# Key.net
KiCad netlist of a schematic drawn in Altium Designer
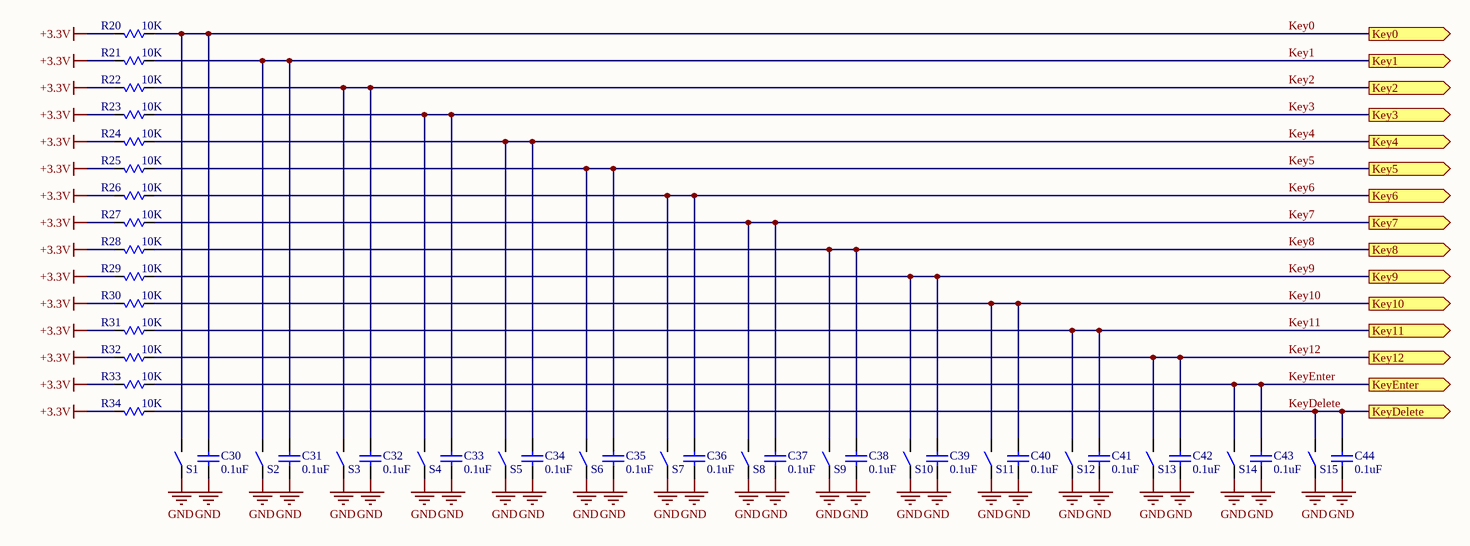
[diagram p0: 电子脚铐手持式主控板_Key.SchDoc]

(export (version "E")
  (design (tool "Eeschema 10.0.6"))
  (components
    (comp (ref "C30")
      (value "0.1uF")
      (footprint "C0603")
      (description "Capacitor")
      (fields (field (name "PUBLISHER") "Altium Limited"))
      (libsource (lib "Miscellaneous Devices") (part "Cap"))
    )
    (comp (ref "C31")
      (value "0.1uF")
      (footprint "C0603")
      (description "Capacitor")
      (fields (field (name "PUBLISHER") "Altium Limited"))
      (libsource (lib "Miscellaneous Devices") (part "Cap"))
    )
    (comp (ref "C32")
      (value "0.1uF")
      (footprint "C0603")
      (description "Capacitor")
      (fields (field (name "PUBLISHER") "Altium Limited"))
      (libsource (lib "Miscellaneous Devices") (part "Cap"))
    )
    (comp (ref "C33")
      (value "0.1uF")
      (footprint "C0603")
      (description "Capacitor")
      (fields (field (name "PUBLISHER") "Altium Limited"))
      (libsource (lib "Miscellaneous Devices") (part "Cap"))
    )
    (comp (ref "C34")
      (value "0.1uF")
      (footprint "C0603")
      (description "Capacitor")
      (fields (field (name "PUBLISHER") "Altium Limited"))
      (libsource (lib "Miscellaneous Devices") (part "Cap"))
    )
    (comp (ref "C35")
      (value "0.1uF")
      (footprint "C0603")
      (description "Capacitor")
      (fields (field (name "PUBLISHER") "Altium Limited"))
      (libsource (lib "Miscellaneous Devices") (part "Cap"))
    )
    (comp (ref "C36")
      (value "0.1uF")
      (footprint "C0603")
      (description "Capacitor")
      (fields (field (name "PUBLISHER") "Altium Limited"))
      (libsource (lib "Miscellaneous Devices") (part "Cap"))
    )
    (comp (ref "C37")
      (value "0.1uF")
      (footprint "C0603")
      (description "Capacitor")
      (fields (field (name "PUBLISHER") "Altium Limited"))
      (libsource (lib "Miscellaneous Devices") (part "Cap"))
    )
    (comp (ref "C38")
      (value "0.1uF")
      (footprint "C0603")
      (description "Capacitor")
      (fields (field (name "PUBLISHER") "Altium Limited"))
      (libsource (lib "Miscellaneous Devices") (part "Cap"))
    )
    (comp (ref "C39")
      (value "0.1uF")
      (footprint "C0603")
      (description "Capacitor")
      (fields (field (name "PUBLISHER") "Altium Limited"))
      (libsource (lib "Miscellaneous Devices") (part "Cap"))
    )
    (comp (ref "C40")
      (value "0.1uF")
      (footprint "C0603")
      (description "Capacitor")
      (fields (field (name "PUBLISHER") "Altium Limited"))
      (libsource (lib "Miscellaneous Devices") (part "Cap"))
    )
    (comp (ref "C41")
      (value "0.1uF")
      (footprint "C0603")
      (description "Capacitor")
      (fields (field (name "PUBLISHER") "Altium Limited"))
      (libsource (lib "Miscellaneous Devices") (part "Cap"))
    )
    (comp (ref "C42")
      (value "0.1uF")
      (footprint "C0603")
      (description "Capacitor")
      (fields (field (name "PUBLISHER") "Altium Limited"))
      (libsource (lib "Miscellaneous Devices") (part "Cap"))
    )
    (comp (ref "C43")
      (value "0.1uF")
      (footprint "C0603")
      (description "Capacitor")
      (fields (field (name "PUBLISHER") "Altium Limited"))
      (libsource (lib "Miscellaneous Devices") (part "Cap"))
    )
    (comp (ref "C44")
      (value "0.1uF")
      (footprint "C0603")
      (description "Capacitor")
      (fields (field (name "PUBLISHER") "Altium Limited"))
      (libsource (lib "Miscellaneous Devices") (part "Cap"))
    )
    (comp (ref "R20")
      (value "10K")
      (footprint "R0603")
      (description "Resistor")
      (fields (field (name "PUBLISHER") "Altium Limited"))
      (libsource (lib "Passive Components Class") (part "RES"))
    )
    (comp (ref "R21")
      (value "10K")
      (footprint "R0603")
      (description "Resistor")
      (fields (field (name "PUBLISHER") "Altium Limited"))
      (libsource (lib "Passive Components Class") (part "RES"))
    )
    (comp (ref "R22")
      (value "10K")
      (footprint "R0603")
      (description "Resistor")
      (fields (field (name "PUBLISHER") "Altium Limited"))
      (libsource (lib "Passive Components Class") (part "RES"))
    )
    (comp (ref "R23")
      (value "10K")
      (footprint "R0603")
      (description "Resistor")
      (fields (field (name "PUBLISHER") "Altium Limited"))
      (libsource (lib "Passive Components Class") (part "RES"))
    )
    (comp (ref "R24")
      (value "10K")
      (footprint "R0603")
      (description "Resistor")
      (fields (field (name "PUBLISHER") "Altium Limited"))
      (libsource (lib "Passive Components Class") (part "RES"))
    )
    (comp (ref "R25")
      (value "10K")
      (footprint "R0603")
      (description "Resistor")
      (fields (field (name "PUBLISHER") "Altium Limited"))
      (libsource (lib "Passive Components Class") (part "RES"))
    )
    (comp (ref "R26")
      (value "10K")
      (footprint "R0603")
      (description "Resistor")
      (fields (field (name "PUBLISHER") "Altium Limited"))
      (libsource (lib "Passive Components Class") (part "RES"))
    )
    (comp (ref "R27")
      (value "10K")
      (footprint "R0603")
      (description "Resistor")
      (fields (field (name "PUBLISHER") "Altium Limited"))
      (libsource (lib "Passive Components Class") (part "RES"))
    )
    (comp (ref "R28")
      (value "10K")
      (footprint "R0603")
      (description "Resistor")
      (fields (field (name "PUBLISHER") "Altium Limited"))
      (libsource (lib "Passive Components Class") (part "RES"))
    )
    (comp (ref "R29")
      (value "10K")
      (footprint "R0603")
      (description "Resistor")
      (fields (field (name "PUBLISHER") "Altium Limited"))
      (libsource (lib "Passive Components Class") (part "RES"))
    )
    (comp (ref "R30")
      (value "10K")
      (footprint "R0603")
      (description "Resistor")
      (fields (field (name "PUBLISHER") "Altium Limited"))
      (libsource (lib "Passive Components Class") (part "RES"))
    )
    (comp (ref "R31")
      (value "10K")
      (footprint "R0603")
      (description "Resistor")
      (fields (field (name "PUBLISHER") "Altium Limited"))
      (libsource (lib "Passive Components Class") (part "RES"))
    )
    (comp (ref "R32")
      (value "10K")
      (footprint "R0603")
      (description "Resistor")
      (fields (field (name "PUBLISHER") "Altium Limited"))
      (libsource (lib "Passive Components Class") (part "RES"))
    )
    (comp (ref "R33")
      (value "10K")
      (footprint "R0603")
      (description "Resistor")
      (fields (field (name "PUBLISHER") "Altium Limited"))
      (libsource (lib "Passive Components Class") (part "RES"))
    )
    (comp (ref "R34")
      (value "10K")
      (footprint "R0603")
      (description "Resistor")
      (fields (field (name "PUBLISHER") "Altium Limited"))
      (libsource (lib "Passive Components Class") (part "RES"))
    )
    (comp (ref "S1") (value "Switch") (footprint "B3F-4055") (libsource (lib "Connector") (part "Sw")))
    (comp (ref "S2") (value "Switch") (footprint "B3F-4055") (libsource (lib "Connector") (part "Sw")))
    (comp (ref "S3") (value "Switch") (footprint "B3F-4055") (libsource (lib "Connector") (part "Sw")))
    (comp (ref "S4") (value "Switch") (footprint "B3F-4055") (libsource (lib "Connector") (part "Sw")))
    (comp (ref "S5") (value "Switch") (footprint "B3F-4055") (libsource (lib "Connector") (part "Sw")))
    (comp (ref "S6") (value "Switch") (footprint "B3F-4055") (libsource (lib "Connector") (part "Sw")))
    (comp (ref "S7") (value "Switch") (footprint "B3F-4055") (libsource (lib "Connector") (part "Sw")))
    (comp (ref "S8") (value "Switch") (footprint "B3F-4055") (libsource (lib "Connector") (part "Sw")))
    (comp (ref "S9") (value "Switch") (footprint "B3F-4055") (libsource (lib "Connector") (part "Sw")))
    (comp (ref "S10") (value "Switch") (footprint "B3F-4055") (libsource (lib "Connector") (part "Sw")))
    (comp (ref "S11") (value "Switch") (footprint "B3F-4055") (libsource (lib "Connector") (part "Sw")))
    (comp (ref "S12") (value "Switch") (footprint "B3F-4055") (libsource (lib "Connector") (part "Sw")))
    (comp (ref "S13") (value "Switch") (footprint "B3F-4055") (libsource (lib "Connector") (part "Sw")))
    (comp (ref "S14") (value "Switch") (footprint "B3F-4055") (libsource (lib "Connector") (part "Sw")))
    (comp (ref "S15") (value "Switch") (footprint "B3F-4055") (libsource (lib "Connector") (part "Sw")))
  )
  (nets
    (net (code "1") (name "+3.3V") (class "Default")
      (node (ref "R20") (pin "2") (pinfunction "2_2") (pintype "passive"))
      (node (ref "R21") (pin "2") (pinfunction "2_2") (pintype "passive"))
      (node (ref "R22") (pin "2") (pinfunction "2_2") (pintype "passive"))
      (node (ref "R23") (pin "2") (pinfunction "2_2") (pintype "passive"))
      (node (ref "R24") (pin "2") (pinfunction "2_2") (pintype "passive"))
      (node (ref "R25") (pin "2") (pinfunction "2_2") (pintype "passive"))
      (node (ref "R26") (pin "2") (pinfunction "2_2") (pintype "passive"))
      (node (ref "R27") (pin "2") (pinfunction "2_2") (pintype "passive"))
      (node (ref "R28") (pin "2") (pinfunction "2_2") (pintype "passive"))
      (node (ref "R29") (pin "2") (pinfunction "2_2") (pintype "passive"))
      (node (ref "R30") (pin "2") (pinfunction "2_2") (pintype "passive"))
      (node (ref "R31") (pin "2") (pinfunction "2_2") (pintype "passive"))
      (node (ref "R32") (pin "2") (pinfunction "2_2") (pintype "passive"))
      (node (ref "R33") (pin "2") (pinfunction "2_2") (pintype "passive"))
      (node (ref "R34") (pin "2") (pinfunction "2_2") (pintype "passive"))
    )
    (net (code "2") (name "/Key0") (class "Default")
      (node (ref "C30") (pin "1") (pinfunction "1_1") (pintype "passive"))
      (node (ref "R20") (pin "1") (pinfunction "1_1") (pintype "passive"))
      (node (ref "S1") (pin "2") (pinfunction "2_2") (pintype "passive"))
    )
    (net (code "3") (name "/Key1") (class "Default")
      (node (ref "C31") (pin "1") (pinfunction "1_1") (pintype "passive"))
      (node (ref "R21") (pin "1") (pinfunction "1_1") (pintype "passive"))
      (node (ref "S2") (pin "2") (pinfunction "2_2") (pintype "passive"))
    )
    (net (code "4") (name "/Key2") (class "Default")
      (node (ref "C32") (pin "1") (pinfunction "1_1") (pintype "passive"))
      (node (ref "R22") (pin "1") (pinfunction "1_1") (pintype "passive"))
      (node (ref "S3") (pin "2") (pinfunction "2_2") (pintype "passive"))
    )
    (net (code "5") (name "/Key3") (class "Default")
      (node (ref "C33") (pin "1") (pinfunction "1_1") (pintype "passive"))
      (node (ref "R23") (pin "1") (pinfunction "1_1") (pintype "passive"))
      (node (ref "S4") (pin "2") (pinfunction "2_2") (pintype "passive"))
    )
    (net (code "6") (name "/Key4") (class "Default")
      (node (ref "C34") (pin "1") (pinfunction "1_1") (pintype "passive"))
      (node (ref "R24") (pin "1") (pinfunction "1_1") (pintype "passive"))
      (node (ref "S5") (pin "2") (pinfunction "2_2") (pintype "passive"))
    )
    (net (code "7") (name "/Key5") (class "Default")
      (node (ref "C35") (pin "1") (pinfunction "1_1") (pintype "passive"))
      (node (ref "R25") (pin "1") (pinfunction "1_1") (pintype "passive"))
      (node (ref "S6") (pin "2") (pinfunction "2_2") (pintype "passive"))
    )
    (net (code "8") (name "/Key6") (class "Default")
      (node (ref "C36") (pin "1") (pinfunction "1_1") (pintype "passive"))
      (node (ref "R26") (pin "1") (pinfunction "1_1") (pintype "passive"))
      (node (ref "S7") (pin "2") (pinfunction "2_2") (pintype "passive"))
    )
    (net (code "9") (name "/Key7") (class "Default")
      (node (ref "C37") (pin "1") (pinfunction "1_1") (pintype "passive"))
      (node (ref "R27") (pin "1") (pinfunction "1_1") (pintype "passive"))
      (node (ref "S8") (pin "2") (pinfunction "2_2") (pintype "passive"))
    )
    (net (code "10") (name "/Key8") (class "Default")
      (node (ref "C38") (pin "1") (pinfunction "1_1") (pintype "passive"))
      (node (ref "R28") (pin "1") (pinfunction "1_1") (pintype "passive"))
      (node (ref "S9") (pin "2") (pinfunction "2_2") (pintype "passive"))
    )
    (net (code "11") (name "/Key9") (class "Default")
      (node (ref "C39") (pin "1") (pinfunction "1_1") (pintype "passive"))
      (node (ref "R29") (pin "1") (pinfunction "1_1") (pintype "passive"))
      (node (ref "S10") (pin "2") (pinfunction "2_2") (pintype "passive"))
    )
    (net (code "12") (name "/Key10") (class "Default")
      (node (ref "C40") (pin "1") (pinfunction "1_1") (pintype "passive"))
      (node (ref "R30") (pin "1") (pinfunction "1_1") (pintype "passive"))
      (node (ref "S11") (pin "2") (pinfunction "2_2") (pintype "passive"))
    )
    (net (code "13") (name "/Key11") (class "Default")
      (node (ref "C41") (pin "1") (pinfunction "1_1") (pintype "passive"))
      (node (ref "R31") (pin "1") (pinfunction "1_1") (pintype "passive"))
      (node (ref "S12") (pin "2") (pinfunction "2_2") (pintype "passive"))
    )
    (net (code "14") (name "/Key12") (class "Default")
      (node (ref "C42") (pin "1") (pinfunction "1_1") (pintype "passive"))
      (node (ref "R32") (pin "1") (pinfunction "1_1") (pintype "passive"))
      (node (ref "S13") (pin "2") (pinfunction "2_2") (pintype "passive"))
    )
    (net (code "15") (name "/KeyDelete") (class "Default")
      (node (ref "C44") (pin "1") (pinfunction "1_1") (pintype "passive"))
      (node (ref "R34") (pin "1") (pinfunction "1_1") (pintype "passive"))
      (node (ref "S15") (pin "2") (pinfunction "2_2") (pintype "passive"))
    )
    (net (code "16") (name "/KeyEnter") (class "Default")
      (node (ref "C43") (pin "1") (pinfunction "1_1") (pintype "passive"))
      (node (ref "R33") (pin "1") (pinfunction "1_1") (pintype "passive"))
      (node (ref "S14") (pin "2") (pinfunction "2_2") (pintype "passive"))
    )
    (net (code "17") (name "GND") (class "Default")
      (node (ref "C30") (pin "2") (pinfunction "2_2") (pintype "passive"))
      (node (ref "C31") (pin "2") (pinfunction "2_2") (pintype "passive"))
      (node (ref "C32") (pin "2") (pinfunction "2_2") (pintype "passive"))
      (node (ref "C33") (pin "2") (pinfunction "2_2") (pintype "passive"))
      (node (ref "C34") (pin "2") (pinfunction "2_2") (pintype "passive"))
      (node (ref "C35") (pin "2") (pinfunction "2_2") (pintype "passive"))
      (node (ref "C36") (pin "2") (pinfunction "2_2") (pintype "passive"))
      (node (ref "C37") (pin "2") (pinfunction "2_2") (pintype "passive"))
      (node (ref "C38") (pin "2") (pinfunction "2_2") (pintype "passive"))
      (node (ref "C39") (pin "2") (pinfunction "2_2") (pintype "passive"))
      (node (ref "C40") (pin "2") (pinfunction "2_2") (pintype "passive"))
      (node (ref "C41") (pin "2") (pinfunction "2_2") (pintype "passive"))
      (node (ref "C42") (pin "2") (pinfunction "2_2") (pintype "passive"))
      (node (ref "C43") (pin "2") (pinfunction "2_2") (pintype "passive"))
      (node (ref "C44") (pin "2") (pinfunction "2_2") (pintype "passive"))
      (node (ref "S1") (pin "1") (pinfunction "1_1") (pintype "passive"))
      (node (ref "S10") (pin "1") (pinfunction "1_1") (pintype "passive"))
      (node (ref "S11") (pin "1") (pinfunction "1_1") (pintype "passive"))
      (node (ref "S12") (pin "1") (pinfunction "1_1") (pintype "passive"))
      (node (ref "S13") (pin "1") (pinfunction "1_1") (pintype "passive"))
      (node (ref "S14") (pin "1") (pinfunction "1_1") (pintype "passive"))
      (node (ref "S15") (pin "1") (pinfunction "1_1") (pintype "passive"))
      (node (ref "S2") (pin "1") (pinfunction "1_1") (pintype "passive"))
      (node (ref "S3") (pin "1") (pinfunction "1_1") (pintype "passive"))
      (node (ref "S4") (pin "1") (pinfunction "1_1") (pintype "passive"))
      (node (ref "S5") (pin "1") (pinfunction "1_1") (pintype "passive"))
      (node (ref "S6") (pin "1") (pinfunction "1_1") (pintype "passive"))
      (node (ref "S7") (pin "1") (pinfunction "1_1") (pintype "passive"))
      (node (ref "S8") (pin "1") (pinfunction "1_1") (pintype "passive"))
      (node (ref "S9") (pin "1") (pinfunction "1_1") (pintype "passive"))
    )
  )
)
